# SmartServoModule_1_0.net
KiCad netlist of a schematic drawn in EAGLE
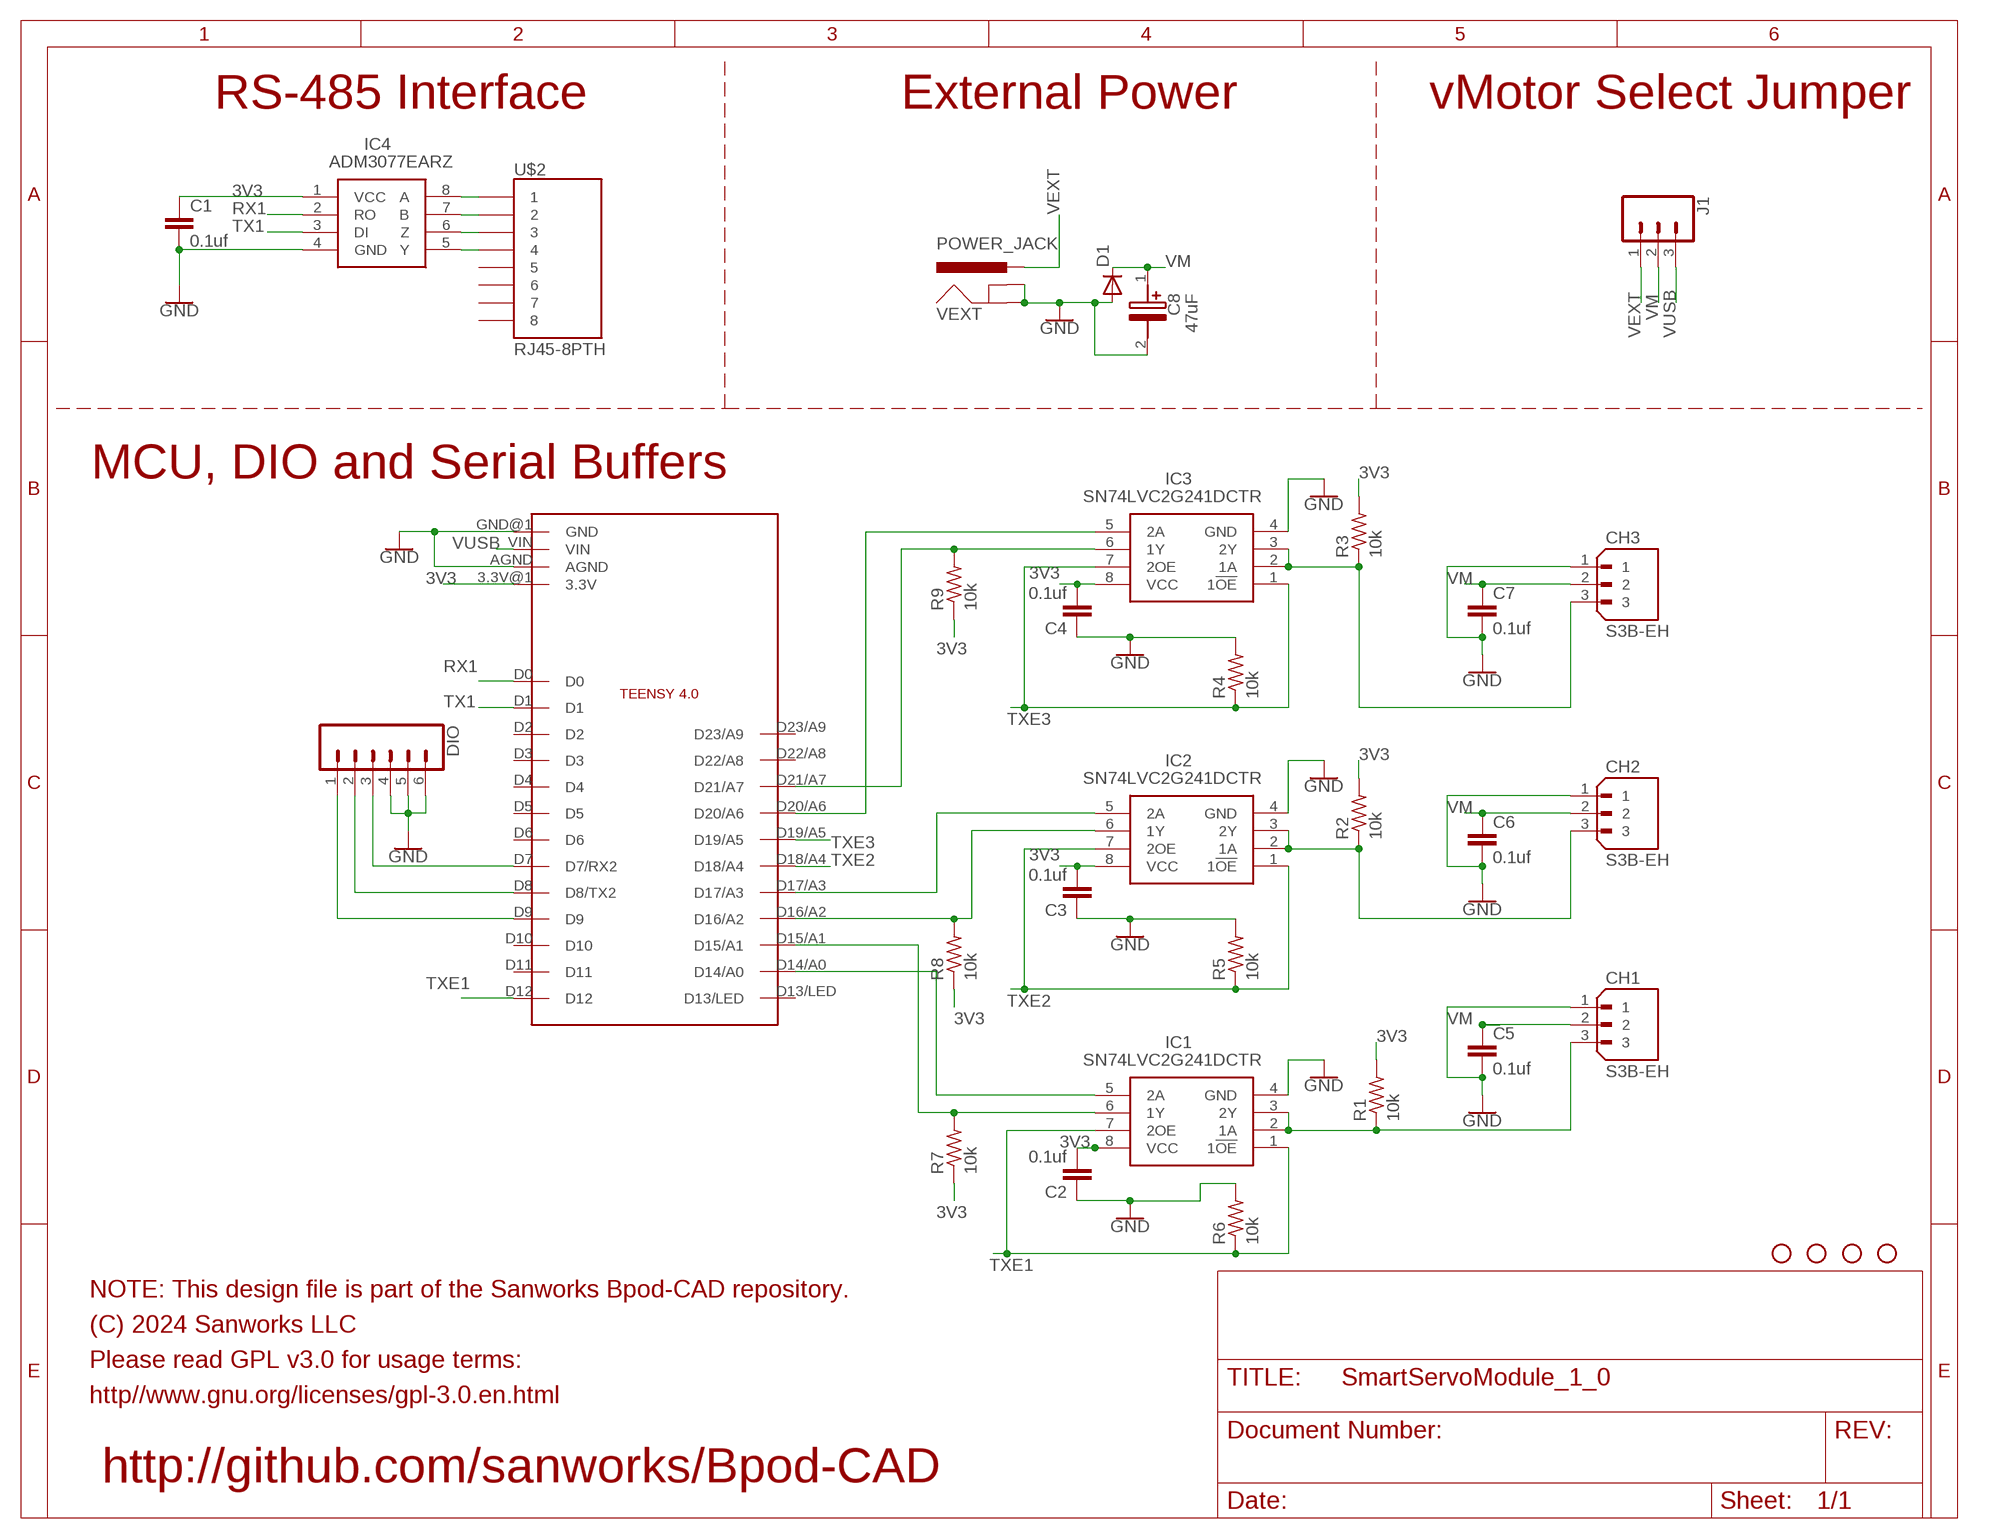
[diagram p0: schematic, sheet 1]

(export (version "E")
  (design (tool "Eeschema 10.0.6"))
  (components
    (comp (ref "C1")
      (value "0.1uf")
      (footprint "eagle-import:0805")
      (libsource (lib "eagle-import") (part "10UF-0805-10V-10%"))
    )
    (comp (ref "C2")
      (value "0.1uf")
      (footprint "eagle-import:0805")
      (libsource (lib "eagle-import") (part "10UF-0805-10V-10%"))
    )
    (comp (ref "C3")
      (value "0.1uf")
      (footprint "eagle-import:0805")
      (libsource (lib "eagle-import") (part "10UF-0805-10V-10%"))
    )
    (comp (ref "C4")
      (value "0.1uf")
      (footprint "eagle-import:0805")
      (libsource (lib "eagle-import") (part "10UF-0805-10V-10%"))
    )
    (comp (ref "C5")
      (value "0.1uf")
      (footprint "eagle-import:0805")
      (libsource (lib "eagle-import") (part "10UF-0805-10V-10%"))
    )
    (comp (ref "C6")
      (value "0.1uf")
      (footprint "eagle-import:0805")
      (libsource (lib "eagle-import") (part "10UF-0805-10V-10%"))
    )
    (comp (ref "C7")
      (value "0.1uf")
      (footprint "eagle-import:0805")
      (libsource (lib "eagle-import") (part "10UF-0805-10V-10%"))
    )
    (comp (ref "C8")
      (value "47uF")
      (footprint "eagle-import:EEHZA1E101XP")
      (fields
        (field (name "MANUFACTURER_PART_NUMBER") "EEH-ZA1V470P")
        (field (name "MOUSER_PART_NUMBER") "667-EEH-ZA1V470P")
      )
      (libsource (lib "eagle-import") (part "EEH-ZA1V470P"))
    )
    (comp (ref "CH1")
      (value "S3B-EH")
      (footprint "eagle-import:JST_S3B-EH")
      (fields (field (name "MANUFACTURER") "JST Sales"))
      (libsource (lib "eagle-import") (part "S3B-EH"))
    )
    (comp (ref "CH2")
      (value "S3B-EH")
      (footprint "eagle-import:JST_S3B-EH")
      (fields (field (name "MANUFACTURER") "JST Sales"))
      (libsource (lib "eagle-import") (part "S3B-EH"))
    )
    (comp (ref "CH3")
      (value "S3B-EH")
      (footprint "eagle-import:JST_S3B-EH")
      (fields (field (name "MANUFACTURER") "JST Sales"))
      (libsource (lib "eagle-import") (part "S3B-EH"))
    )
    (comp (ref "D1")
      (value "DIODE-DO214AA")
      (footprint "eagle-import:DO214AA")
      (libsource (lib "eagle-import") (part "DIODE-DO214AA"))
    )
    (comp (ref "DIO")
      (value "CONN_063.5MM-6")
      (footprint "eagle-import:SCREWTERMINAL-3.5MM-6")
      (libsource (lib "eagle-import") (part "CONN_063.5MM-6"))
    )
    (comp (ref "H1")
      (value "STAND-OFF")
      (footprint "eagle-import:STAND-OFF")
      (libsource (lib "eagle-import") (part "STAND-OFF"))
    )
    (comp (ref "H2")
      (value "STAND-OFF")
      (footprint "eagle-import:STAND-OFF")
      (libsource (lib "eagle-import") (part "STAND-OFF"))
    )
    (comp (ref "H3")
      (value "STAND-OFF")
      (footprint "eagle-import:STAND-OFF")
      (libsource (lib "eagle-import") (part "STAND-OFF"))
    )
    (comp (ref "H4")
      (value "STAND-OFF")
      (footprint "eagle-import:STAND-OFF")
      (libsource (lib "eagle-import") (part "STAND-OFF"))
    )
    (comp (ref "IC1")
      (value "SN74LVC2G241DCTR")
      (footprint "eagle-import:SOP65P400X130-8N")
      (fields (field (name "MOUSER_PART_NUMBER") "595-SN74LVC2G241DCTR"))
      (libsource (lib "eagle-import") (part "SN74LVC2G241DCTR"))
    )
    (comp (ref "IC2")
      (value "SN74LVC2G241DCTR")
      (footprint "eagle-import:SOP65P400X130-8N")
      (fields (field (name "MOUSER_PART_NUMBER") "595-SN74LVC2G241DCTR"))
      (libsource (lib "eagle-import") (part "SN74LVC2G241DCTR"))
    )
    (comp (ref "IC3")
      (value "SN74LVC2G241DCTR")
      (footprint "eagle-import:SOP65P400X130-8N")
      (fields (field (name "MOUSER_PART_NUMBER") "595-SN74LVC2G241DCTR"))
      (libsource (lib "eagle-import") (part "SN74LVC2G241DCTR"))
    )
    (comp (ref "IC4")
      (value "ADM3077EARZ")
      (footprint "eagle-import:SOIC127P600X175-8N")
      (fields (field (name "MOUSER_PART_NUMBER") "584-ADM3077EARZ"))
      (libsource (lib "eagle-import") (part "ADM3077EARZ"))
    )
    (comp (ref "J1")
      (value "CONN_03LOCK")
      (footprint "eagle-import:1X03_LOCK")
      (libsource (lib "eagle-import") (part "CONN_03LOCK"))
    )
    (comp (ref "MC1")
      (value "TEENSY4.0_SIMPLE_NO_VUSB")
      (footprint "eagle-import:TEENSY4.0_SIMPLE_NO_VUSB")
      (libsource (lib "eagle-import") (part "TEENSY4.0_SIMPLE_NO_VUSB"))
    )
    (comp (ref "R1")
      (value "10k")
      (footprint "eagle-import:R0805")
      (libsource (lib "eagle-import") (part "R-US_R0805"))
    )
    (comp (ref "R2")
      (value "10k")
      (footprint "eagle-import:R0805")
      (libsource (lib "eagle-import") (part "R-US_R0805"))
    )
    (comp (ref "R3")
      (value "10k")
      (footprint "eagle-import:R0805")
      (libsource (lib "eagle-import") (part "R-US_R0805"))
    )
    (comp (ref "R4")
      (value "10k")
      (footprint "eagle-import:R0805")
      (libsource (lib "eagle-import") (part "R-US_R0805"))
    )
    (comp (ref "R5")
      (value "10k")
      (footprint "eagle-import:R0805")
      (libsource (lib "eagle-import") (part "R-US_R0805"))
    )
    (comp (ref "R6")
      (value "10k")
      (footprint "eagle-import:R0805")
      (libsource (lib "eagle-import") (part "R-US_R0805"))
    )
    (comp (ref "R7")
      (value "10k")
      (footprint "eagle-import:R0805")
      (libsource (lib "eagle-import") (part "R-US_R0805"))
    )
    (comp (ref "R8")
      (value "10k")
      (footprint "eagle-import:R0805")
      (libsource (lib "eagle-import") (part "R-US_R0805"))
    )
    (comp (ref "R9")
      (value "10k")
      (footprint "eagle-import:R0805")
      (libsource (lib "eagle-import") (part "R-US_R0805"))
    )
    (comp (ref "U$2")
      (value "RJ45-8PTH")
      (footprint "eagle-import:RJ45-8")
      (libsource (lib "eagle-import") (part "RJ45-8PTH"))
    )
    (comp (ref "VEXT")
      (value "POWER_JACK")
      (footprint "eagle-import:POWER_JACK_PTH")
      (libsource (lib "eagle-import") (part "POWER_JACK"))
    )
  )
  (nets
    (net (code "1") (name "/3V3") (class "Default")
      (node (ref "C1") (pin "1") (pinfunction "1_1") (pintype "passive"))
      (node (ref "C2") (pin "2") (pinfunction "2_2") (pintype "passive"))
      (node (ref "C3") (pin "2") (pinfunction "2_2") (pintype "passive"))
      (node (ref "C4") (pin "2") (pinfunction "2_2") (pintype "passive"))
      (node (ref "IC1") (pin "8") (pinfunction "VCC_8") (pintype "bidirectional"))
      (node (ref "IC2") (pin "8") (pinfunction "VCC_8") (pintype "bidirectional"))
      (node (ref "IC3") (pin "8") (pinfunction "VCC_8") (pintype "bidirectional"))
      (node (ref "IC4") (pin "1") (pinfunction "VCC_1") (pintype "bidirectional"))
      (node (ref "MC1") (pin "3.3V@1") (pinfunction "3.3V_3.3V@1") (pintype "bidirectional"))
      (node (ref "R1") (pin "2") (pinfunction "2_2") (pintype "passive"))
      (node (ref "R2") (pin "2") (pinfunction "2_2") (pintype "passive"))
      (node (ref "R3") (pin "2") (pinfunction "2_2") (pintype "passive"))
      (node (ref "R7") (pin "1") (pinfunction "1_1") (pintype "passive"))
      (node (ref "R8") (pin "1") (pinfunction "1_1") (pintype "passive"))
      (node (ref "R9") (pin "1") (pinfunction "1_1") (pintype "passive"))
    )
    (net (code "2") (name "/RX1") (class "Default")
      (node (ref "IC4") (pin "2") (pinfunction "RO_2") (pintype "bidirectional"))
      (node (ref "MC1") (pin "D0") (pinfunction "D0_D0") (pintype "bidirectional"))
    )
    (net (code "3") (name "/TX1") (class "Default")
      (node (ref "IC4") (pin "3") (pinfunction "DI_3") (pintype "bidirectional"))
      (node (ref "MC1") (pin "D1") (pinfunction "D1_D1") (pintype "bidirectional"))
    )
    (net (code "4") (name "/TXE1") (class "Default")
      (node (ref "IC1") (pin "1") (pinfunction "1~{OE}_1") (pintype "bidirectional"))
      (node (ref "IC1") (pin "7") (pinfunction "2OE_7") (pintype "bidirectional"))
      (node (ref "MC1") (pin "D12") (pinfunction "D12_D12") (pintype "bidirectional"))
      (node (ref "R6") (pin "1") (pinfunction "1_1") (pintype "passive"))
    )
    (net (code "5") (name "/TXE2") (class "Default")
      (node (ref "IC2") (pin "1") (pinfunction "1~{OE}_1") (pintype "bidirectional"))
      (node (ref "IC2") (pin "7") (pinfunction "2OE_7") (pintype "bidirectional"))
      (node (ref "MC1") (pin "D18/A4") (pinfunction "D18/A4_D18/A4") (pintype "bidirectional"))
      (node (ref "R5") (pin "1") (pinfunction "1_1") (pintype "passive"))
    )
    (net (code "6") (name "/TXE3") (class "Default")
      (node (ref "IC3") (pin "1") (pinfunction "1~{OE}_1") (pintype "bidirectional"))
      (node (ref "IC3") (pin "7") (pinfunction "2OE_7") (pintype "bidirectional"))
      (node (ref "MC1") (pin "D19/A5") (pinfunction "D19/A5_D19/A5") (pintype "bidirectional"))
      (node (ref "R4") (pin "1") (pinfunction "1_1") (pintype "passive"))
    )
    (net (code "7") (name "/VEXT") (class "Default")
      (node (ref "J1") (pin "1") (pinfunction "1_1") (pintype "passive"))
      (node (ref "VEXT") (pin "PWR") (pinfunction "PWR_PWR") (pintype "bidirectional"))
    )
    (net (code "8") (name "/VM") (class "Default")
      (node (ref "C5") (pin "1") (pinfunction "1_1") (pintype "passive"))
      (node (ref "C6") (pin "1") (pinfunction "1_1") (pintype "passive"))
      (node (ref "C7") (pin "1") (pinfunction "1_1") (pintype "passive"))
      (node (ref "C8") (pin "1") (pinfunction "+_1") (pintype "bidirectional"))
      (node (ref "CH1") (pin "2") (pinfunction "2_2") (pintype "passive"))
      (node (ref "CH2") (pin "2") (pinfunction "2_2") (pintype "passive"))
      (node (ref "CH3") (pin "2") (pinfunction "2_2") (pintype "passive"))
      (node (ref "D1") (pin "C") (pinfunction "C_C") (pintype "passive"))
      (node (ref "J1") (pin "2") (pinfunction "2_2") (pintype "passive"))
    )
    (net (code "9") (name "/VUSB") (class "Default")
      (node (ref "J1") (pin "3") (pinfunction "3_3") (pintype "passive"))
      (node (ref "MC1") (pin "VIN") (pinfunction "VIN_VIN") (pintype "bidirectional"))
    )
    (net (code "10") (name "GND") (class "Default")
      (node (ref "C1") (pin "2") (pinfunction "2_2") (pintype "passive"))
      (node (ref "C2") (pin "1") (pinfunction "1_1") (pintype "passive"))
      (node (ref "C3") (pin "1") (pinfunction "1_1") (pintype "passive"))
      (node (ref "C4") (pin "1") (pinfunction "1_1") (pintype "passive"))
      (node (ref "C5") (pin "2") (pinfunction "2_2") (pintype "passive"))
      (node (ref "C6") (pin "2") (pinfunction "2_2") (pintype "passive"))
      (node (ref "C7") (pin "2") (pinfunction "2_2") (pintype "passive"))
      (node (ref "C8") (pin "2") (pinfunction "-_2") (pintype "bidirectional"))
      (node (ref "CH1") (pin "1") (pinfunction "1_1") (pintype "passive"))
      (node (ref "CH2") (pin "1") (pinfunction "1_1") (pintype "passive"))
      (node (ref "CH3") (pin "1") (pinfunction "1_1") (pintype "passive"))
      (node (ref "D1") (pin "A") (pinfunction "A_A") (pintype "passive"))
      (node (ref "DIO") (pin "4") (pinfunction "4_4") (pintype "passive"))
      (node (ref "DIO") (pin "5") (pinfunction "5_5") (pintype "passive"))
      (node (ref "DIO") (pin "6") (pinfunction "6_6") (pintype "passive"))
      (node (ref "IC1") (pin "4") (pinfunction "GND_4") (pintype "bidirectional"))
      (node (ref "IC2") (pin "4") (pinfunction "GND_4") (pintype "bidirectional"))
      (node (ref "IC3") (pin "4") (pinfunction "GND_4") (pintype "bidirectional"))
      (node (ref "IC4") (pin "4") (pinfunction "GND_4") (pintype "bidirectional"))
      (node (ref "MC1") (pin "AGND") (pinfunction "AGND_AGND") (pintype "bidirectional"))
      (node (ref "MC1") (pin "GND@1") (pinfunction "GND_GND@1") (pintype "bidirectional"))
      (node (ref "R4") (pin "2") (pinfunction "2_2") (pintype "passive"))
      (node (ref "R5") (pin "2") (pinfunction "2_2") (pintype "passive"))
      (node (ref "R6") (pin "2") (pinfunction "2_2") (pintype "passive"))
      (node (ref "VEXT") (pin "GND") (pinfunction "GND_GND") (pintype "bidirectional"))
      (node (ref "VEXT") (pin "GNDBREAK") (pinfunction "GNDBREAK_GNDBREAK") (pintype "bidirectional"))
    )
    (net (code "11") (name "Net-(DIO-Pad1)") (class "Default")
      (node (ref "DIO") (pin "1") (pinfunction "1_1") (pintype "passive"))
      (node (ref "MC1") (pin "D9") (pinfunction "D9_D9") (pintype "bidirectional"))
    )
    (net (code "12") (name "Net-(IC1-1A)") (class "Default")
      (node (ref "CH1") (pin "3") (pinfunction "3_3") (pintype "passive"))
      (node (ref "IC1") (pin "2") (pinfunction "1A_2") (pintype "bidirectional"))
      (node (ref "IC1") (pin "3") (pinfunction "2Y_3") (pintype "bidirectional"))
      (node (ref "R1") (pin "1") (pinfunction "1_1") (pintype "passive"))
    )
    (net (code "13") (name "Net-(IC1-1Y)") (class "Default")
      (node (ref "IC1") (pin "6") (pinfunction "1Y_6") (pintype "bidirectional"))
      (node (ref "MC1") (pin "D15/A1") (pinfunction "D15/A1_D15/A1") (pintype "bidirectional"))
      (node (ref "R7") (pin "2") (pinfunction "2_2") (pintype "passive"))
    )
    (net (code "14") (name "Net-(IC1-2A)") (class "Default")
      (node (ref "IC1") (pin "5") (pinfunction "2A_5") (pintype "bidirectional"))
      (node (ref "MC1") (pin "D14/A0") (pinfunction "D14/A0_D14/A0") (pintype "bidirectional"))
    )
    (net (code "15") (name "Net-(IC2-1A)") (class "Default")
      (node (ref "CH2") (pin "3") (pinfunction "3_3") (pintype "passive"))
      (node (ref "IC2") (pin "2") (pinfunction "1A_2") (pintype "bidirectional"))
      (node (ref "IC2") (pin "3") (pinfunction "2Y_3") (pintype "bidirectional"))
      (node (ref "R2") (pin "1") (pinfunction "1_1") (pintype "passive"))
    )
    (net (code "16") (name "Net-(IC2-1Y)") (class "Default")
      (node (ref "IC2") (pin "6") (pinfunction "1Y_6") (pintype "bidirectional"))
      (node (ref "MC1") (pin "D16/A2") (pinfunction "D16/A2_D16/A2") (pintype "bidirectional"))
      (node (ref "R8") (pin "2") (pinfunction "2_2") (pintype "passive"))
    )
    (net (code "17") (name "Net-(IC2-2A)") (class "Default")
      (node (ref "IC2") (pin "5") (pinfunction "2A_5") (pintype "bidirectional"))
      (node (ref "MC1") (pin "D17/A3") (pinfunction "D17/A3_D17/A3") (pintype "bidirectional"))
    )
    (net (code "18") (name "Net-(IC3-1A)") (class "Default")
      (node (ref "CH3") (pin "3") (pinfunction "3_3") (pintype "passive"))
      (node (ref "IC3") (pin "2") (pinfunction "1A_2") (pintype "bidirectional"))
      (node (ref "IC3") (pin "3") (pinfunction "2Y_3") (pintype "bidirectional"))
      (node (ref "R3") (pin "1") (pinfunction "1_1") (pintype "passive"))
    )
    (net (code "19") (name "Net-(IC3-1Y)") (class "Default")
      (node (ref "IC3") (pin "6") (pinfunction "1Y_6") (pintype "bidirectional"))
      (node (ref "MC1") (pin "D21/A7") (pinfunction "D21/A7_D21/A7") (pintype "bidirectional"))
      (node (ref "R9") (pin "2") (pinfunction "2_2") (pintype "passive"))
    )
    (net (code "20") (name "Net-(IC3-2A)") (class "Default")
      (node (ref "IC3") (pin "5") (pinfunction "2A_5") (pintype "bidirectional"))
      (node (ref "MC1") (pin "D20/A6") (pinfunction "D20/A6_D20/A6") (pintype "bidirectional"))
    )
    (net (code "21") (name "Net-(IC4-A)") (class "Default")
      (node (ref "IC4") (pin "8") (pinfunction "A_8") (pintype "bidirectional"))
      (node (ref "U$2") (pin "1") (pinfunction "1_1") (pintype "bidirectional"))
    )
    (net (code "22") (name "Net-(IC4-B)") (class "Default")
      (node (ref "IC4") (pin "7") (pinfunction "B_7") (pintype "bidirectional"))
      (node (ref "U$2") (pin "2") (pinfunction "2_2") (pintype "bidirectional"))
    )
    (net (code "23") (name "Net-(IC4-Y)") (class "Default")
      (node (ref "IC4") (pin "5") (pinfunction "Y_5") (pintype "bidirectional"))
      (node (ref "U$2") (pin "4") (pinfunction "4_4") (pintype "bidirectional"))
    )
    (net (code "24") (name "Net-(IC4-Z)") (class "Default")
      (node (ref "IC4") (pin "6") (pinfunction "Z_6") (pintype "bidirectional"))
      (node (ref "U$2") (pin "3") (pinfunction "3_3") (pintype "bidirectional"))
    )
    (net (code "25") (name "Net-(MC1-D7{slash}RX2)") (class "Default")
      (node (ref "DIO") (pin "3") (pinfunction "3_3") (pintype "passive"))
      (node (ref "MC1") (pin "D7") (pinfunction "D7/RX2_D7") (pintype "bidirectional"))
    )
    (net (code "26") (name "Net-(MC1-D8{slash}TX2)") (class "Default")
      (node (ref "DIO") (pin "2") (pinfunction "2_2") (pintype "passive"))
      (node (ref "MC1") (pin "D8") (pinfunction "D8/TX2_D8") (pintype "bidirectional"))
    )
    (net (code "27") (name "unconnected-(MC1-PadD2)") (class "Default")
      (node (ref "MC1") (pin "D2") (pinfunction "D2_D2") (pintype "bidirectional"))
    )
    (net (code "28") (name "unconnected-(MC1-PadD3)") (class "Default")
      (node (ref "MC1") (pin "D3") (pinfunction "D3_D3") (pintype "bidirectional"))
    )
    (net (code "29") (name "unconnected-(MC1-PadD4)") (class "Default")
      (node (ref "MC1") (pin "D4") (pinfunction "D4_D4") (pintype "bidirectional"))
    )
    (net (code "30") (name "unconnected-(MC1-PadD5)") (class "Default")
      (node (ref "MC1") (pin "D5") (pinfunction "D5_D5") (pintype "bidirectional"))
    )
    (net (code "31") (name "unconnected-(MC1-PadD6)") (class "Default")
      (node (ref "MC1") (pin "D6") (pinfunction "D6_D6") (pintype "bidirectional"))
    )
    (net (code "32") (name "unconnected-(MC1-PadD10)") (class "Default")
      (node (ref "MC1") (pin "D10") (pinfunction "D10_D10") (pintype "bidirectional"))
    )
    (net (code "33") (name "unconnected-(MC1-PadD11)") (class "Default")
      (node (ref "MC1") (pin "D11") (pinfunction "D11_D11") (pintype "bidirectional"))
    )
    (net (code "34") (name "unconnected-(MC1-PadD13{slash}LED)") (class "Default")
      (node (ref "MC1") (pin "D13/LED") (pinfunction "D13/LED_D13/LED") (pintype "bidirectional"))
    )
    (net (code "35") (name "unconnected-(MC1-PadD22{slash}A8)") (class "Default")
      (node (ref "MC1") (pin "D22/A8") (pinfunction "D22/A8_D22/A8") (pintype "bidirectional"))
    )
    (net (code "36") (name "unconnected-(MC1-PadD23{slash}A9)") (class "Default")
      (node (ref "MC1") (pin "D23/A9") (pinfunction "D23/A9_D23/A9") (pintype "bidirectional"))
    )
    (net (code "37") (name "unconnected-(U$2-Pad5)") (class "Default")
      (node (ref "U$2") (pin "5") (pinfunction "5_5") (pintype "bidirectional"))
    )
    (net (code "38") (name "unconnected-(U$2-Pad6)") (class "Default")
      (node (ref "U$2") (pin "6") (pinfunction "6_6") (pintype "bidirectional"))
    )
    (net (code "39") (name "unconnected-(U$2-Pad7)") (class "Default")
      (node (ref "U$2") (pin "7") (pinfunction "7_7") (pintype "bidirectional"))
    )
    (net (code "40") (name "unconnected-(U$2-Pad8)") (class "Default")
      (node (ref "U$2") (pin "8") (pinfunction "8_8") (pintype "bidirectional"))
    )
  )
)
